# rc360detector_102415_7_15.net
KiCad netlist of a schematic drawn in EAGLE
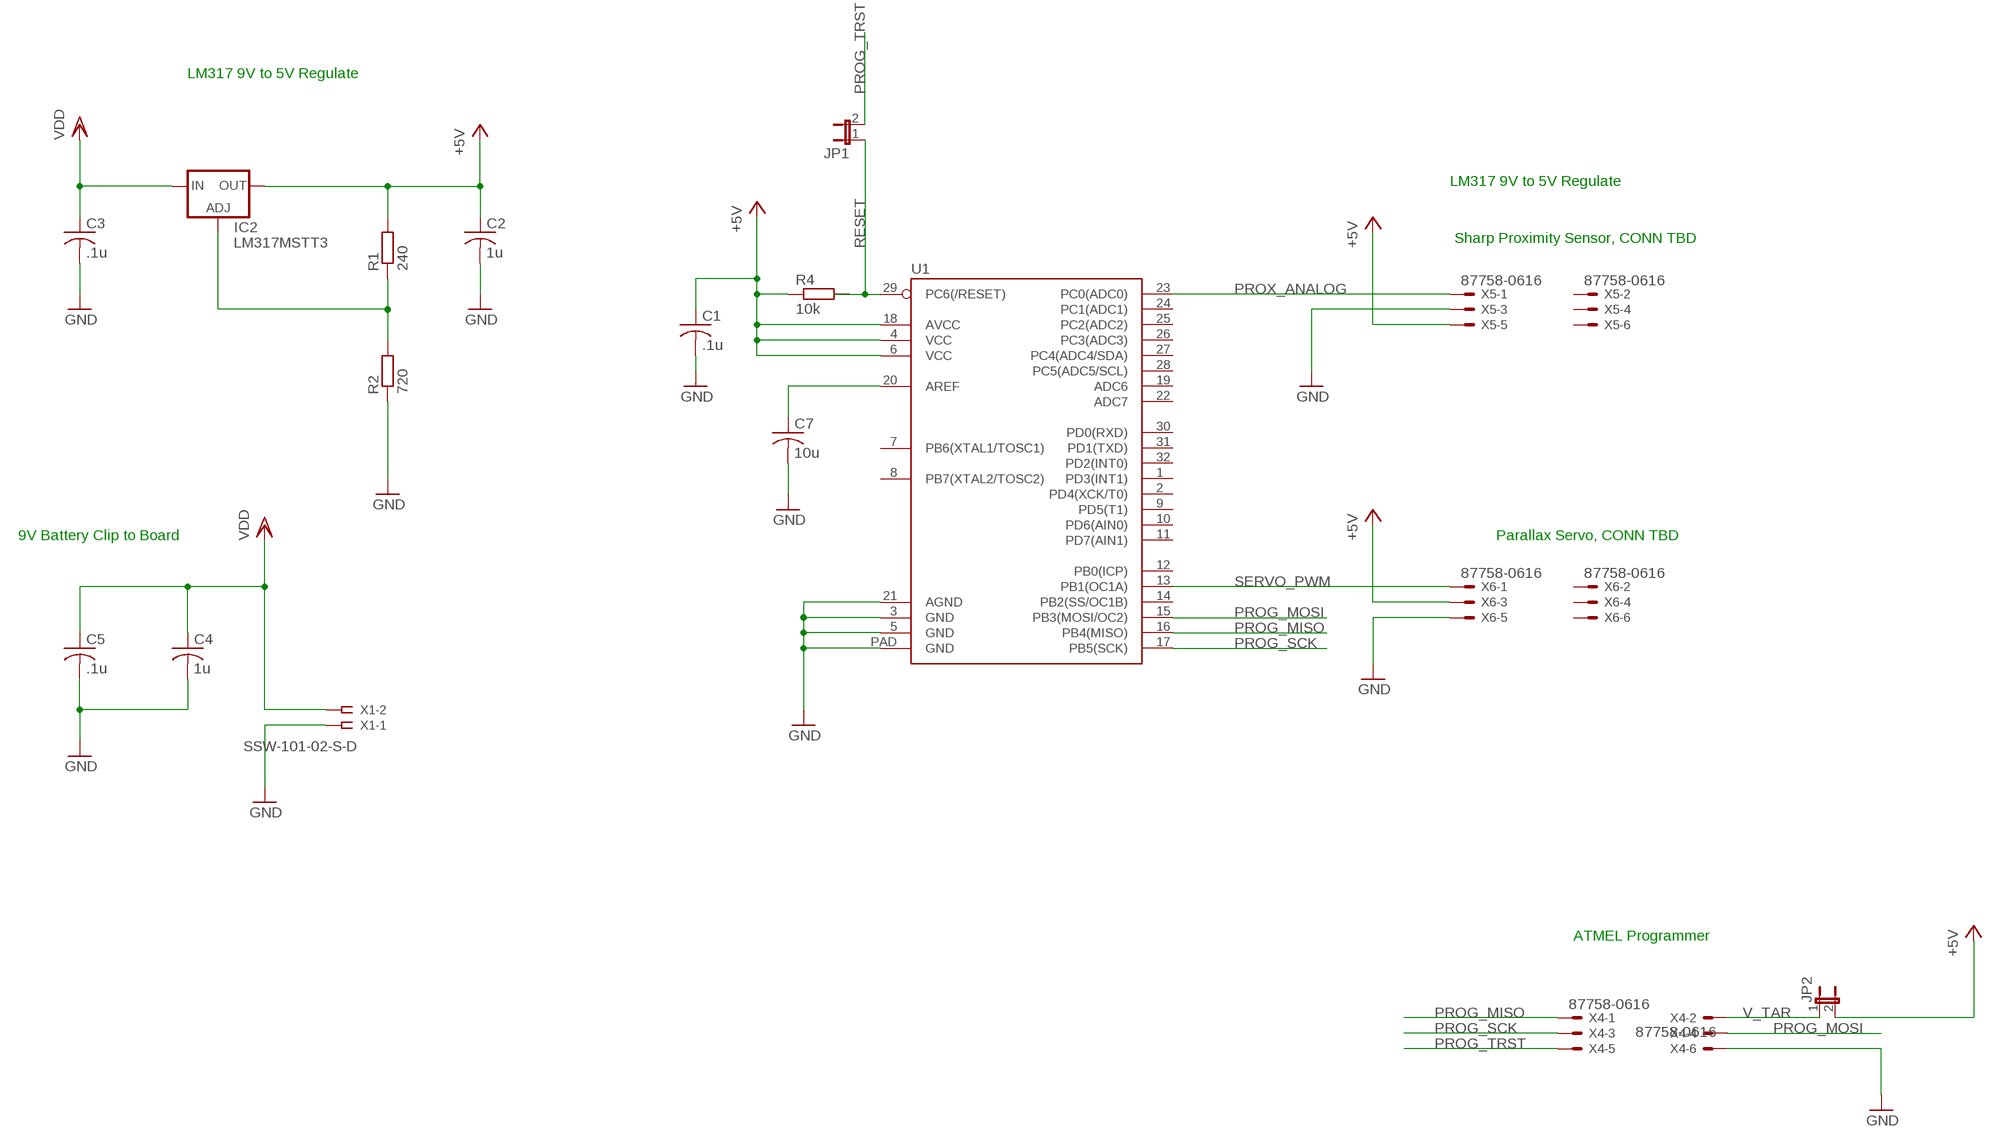
[diagram p0: schematic, sheet 1]

(export (version "E")
  (design (tool "Eeschema 10.0.6"))
  (components
    (comp (ref "C1")
      (value ".1u")
      (footprint "eagle-import:C0603")
      (libsource (lib "eagle-import") (part "C-USC0603"))
    )
    (comp (ref "C2")
      (value "1u")
      (footprint "eagle-import:C0603")
      (libsource (lib "eagle-import") (part "C-USC0603"))
    )
    (comp (ref "C3")
      (value ".1u")
      (footprint "eagle-import:C0603")
      (libsource (lib "eagle-import") (part "C-USC0603"))
    )
    (comp (ref "C4")
      (value "1u")
      (footprint "eagle-import:C0603")
      (libsource (lib "eagle-import") (part "C-USC0603"))
    )
    (comp (ref "C5")
      (value ".1u")
      (footprint "eagle-import:C0603")
      (libsource (lib "eagle-import") (part "C-USC0603"))
    )
    (comp (ref "C7")
      (value "10u")
      (footprint "eagle-import:C0603")
      (libsource (lib "eagle-import") (part "C-USC0603"))
    )
    (comp (ref "IC2")
      (value "LM317MSTT3")
      (footprint "eagle-import:SOT223")
      (libsource (lib "eagle-import") (part "LM317?MSTT3"))
    )
    (comp (ref "JP1")
      (value "JP1E")
      (footprint "eagle-import:JP1")
      (libsource (lib "eagle-import") (part "JP1E"))
    )
    (comp (ref "JP2")
      (value "JP1E")
      (footprint "eagle-import:JP1")
      (libsource (lib "eagle-import") (part "JP1E"))
    )
    (comp (ref "R1")
      (value "240")
      (footprint "eagle-import:R0603")
      (libsource (lib "eagle-import") (part "R-EU_R0603"))
    )
    (comp (ref "R2")
      (value "720")
      (footprint "eagle-import:R0603")
      (libsource (lib "eagle-import") (part "R-EU_R0603"))
    )
    (comp (ref "R4")
      (value "10k")
      (footprint "eagle-import:R0603")
      (libsource (lib "eagle-import") (part "R-EU_R0603"))
    )
    (comp (ref "U1")
      (value "ATMEGA328P_MLFMLF32")
      (footprint "eagle-import:MLF32-PAD")
      (libsource (lib "eagle-import") (part "ATMEGA328P_MLFMLF32"))
    )
    (comp (ref "X1")
      (value "SSW-101-02-S-D")
      (footprint "eagle-import:SSW-101-02-S-D")
      (libsource (lib "eagle-import") (part "SSW-101-02-S-D"))
    )
    (comp (ref "X4")
      (value "87758-0616")
      (footprint "eagle-import:87758-0616")
      (libsource (lib "eagle-import") (part "87758-0616"))
    )
    (comp (ref "X5")
      (value "87758-0616")
      (footprint "eagle-import:87758-0616")
      (libsource (lib "eagle-import") (part "87758-0616"))
    )
    (comp (ref "X6")
      (value "87758-0616")
      (footprint "eagle-import:87758-0616")
      (libsource (lib "eagle-import") (part "87758-0616"))
    )
  )
  (nets
    (net (code "1") (name "+5V") (class "Default")
      (node (ref "C1") (pin "1") (pinfunction "1_1") (pintype "passive"))
      (node (ref "C2") (pin "1") (pinfunction "1_1") (pintype "passive"))
      (node (ref "IC2") (pin "4") (pinfunction "OUT_4") (pintype "passive"))
      (node (ref "JP2") (pin "2") (pinfunction "2_2") (pintype "passive"))
      (node (ref "R1") (pin "2") (pinfunction "2_2") (pintype "passive"))
      (node (ref "R4") (pin "1") (pinfunction "1_1") (pintype "passive"))
      (node (ref "U1") (pin "18") (pinfunction "AVCC_18") (pintype "bidirectional"))
      (node (ref "U1") (pin "4") (pinfunction "VCC_4") (pintype "bidirectional"))
      (node (ref "U1") (pin "6") (pinfunction "VCC_6") (pintype "bidirectional"))
      (node (ref "X5") (pin "5") (pinfunction "S_5") (pintype "passive"))
      (node (ref "X6") (pin "3") (pinfunction "S_3") (pintype "passive"))
    )
    (net (code "2") (name "/PROG_MISO") (class "Default")
      (node (ref "U1") (pin "16") (pinfunction "PB4(MISO)_16") (pintype "bidirectional"))
      (node (ref "X4") (pin "1") (pinfunction "S_1") (pintype "passive"))
    )
    (net (code "3") (name "/PROG_MOSI") (class "Default")
      (node (ref "U1") (pin "15") (pinfunction "PB3(MOSI/OC2)_15") (pintype "bidirectional"))
      (node (ref "X4") (pin "4") (pinfunction "S_4") (pintype "passive"))
    )
    (net (code "4") (name "/PROG_SCK") (class "Default")
      (node (ref "U1") (pin "17") (pinfunction "PB5(SCK)_17") (pintype "bidirectional"))
      (node (ref "X4") (pin "3") (pinfunction "S_3") (pintype "passive"))
    )
    (net (code "5") (name "/PROG_TRST") (class "Default")
      (node (ref "JP1") (pin "2") (pinfunction "2_2") (pintype "passive"))
      (node (ref "X4") (pin "5") (pinfunction "S_5") (pintype "passive"))
    )
    (net (code "6") (name "/PROX_ANALOG") (class "Default")
      (node (ref "U1") (pin "23") (pinfunction "PC0(ADC0)_23") (pintype "bidirectional"))
      (node (ref "X5") (pin "1") (pinfunction "S_1") (pintype "passive"))
    )
    (net (code "7") (name "/RESET") (class "Default")
      (node (ref "JP1") (pin "1") (pinfunction "1_1") (pintype "passive"))
      (node (ref "R4") (pin "2") (pinfunction "2_2") (pintype "passive"))
      (node (ref "U1") (pin "29") (pinfunction "PC6(/RESET)_29") (pintype "bidirectional"))
    )
    (net (code "8") (name "/SERVO_PWM") (class "Default")
      (node (ref "U1") (pin "13") (pinfunction "PB1(OC1A)_13") (pintype "bidirectional"))
      (node (ref "X6") (pin "1") (pinfunction "S_1") (pintype "passive"))
    )
    (net (code "9") (name "/V_TAR") (class "Default")
      (node (ref "JP2") (pin "1") (pinfunction "1_1") (pintype "passive"))
      (node (ref "X4") (pin "2") (pinfunction "S_2") (pintype "passive"))
    )
    (net (code "10") (name "GND") (class "Default")
      (node (ref "C1") (pin "2") (pinfunction "2_2") (pintype "passive"))
      (node (ref "C2") (pin "2") (pinfunction "2_2") (pintype "passive"))
      (node (ref "C3") (pin "2") (pinfunction "2_2") (pintype "passive"))
      (node (ref "C4") (pin "2") (pinfunction "2_2") (pintype "passive"))
      (node (ref "C5") (pin "2") (pinfunction "2_2") (pintype "passive"))
      (node (ref "C7") (pin "2") (pinfunction "2_2") (pintype "passive"))
      (node (ref "R2") (pin "1") (pinfunction "1_1") (pintype "passive"))
      (node (ref "U1") (pin "21") (pinfunction "AGND_21") (pintype "bidirectional"))
      (node (ref "U1") (pin "3") (pinfunction "GND_3") (pintype "bidirectional"))
      (node (ref "U1") (pin "5") (pinfunction "GND_5") (pintype "bidirectional"))
      (node (ref "U1") (pin "PAD") (pinfunction "GND_PAD") (pintype "bidirectional"))
      (node (ref "X1") (pin "1") (pinfunction "1_1") (pintype "passive"))
      (node (ref "X4") (pin "6") (pinfunction "S_6") (pintype "passive"))
      (node (ref "X5") (pin "3") (pinfunction "S_3") (pintype "passive"))
      (node (ref "X6") (pin "5") (pinfunction "S_5") (pintype "passive"))
    )
    (net (code "11") (name "Net-(IC2-ADJ)") (class "Default")
      (node (ref "IC2") (pin "1") (pinfunction "ADJ_1") (pintype "input"))
      (node (ref "R1") (pin "1") (pinfunction "1_1") (pintype "passive"))
      (node (ref "R2") (pin "2") (pinfunction "2_2") (pintype "passive"))
    )
    (net (code "12") (name "Net-(U1-AREF)") (class "Default")
      (node (ref "C7") (pin "1") (pinfunction "1_1") (pintype "passive"))
      (node (ref "U1") (pin "20") (pinfunction "AREF_20") (pintype "bidirectional"))
    )
    (net (code "13") (name "VDD") (class "Default")
      (node (ref "C3") (pin "1") (pinfunction "1_1") (pintype "passive"))
      (node (ref "C4") (pin "1") (pinfunction "1_1") (pintype "passive"))
      (node (ref "C5") (pin "1") (pinfunction "1_1") (pintype "passive"))
      (node (ref "IC2") (pin "3") (pinfunction "IN_3") (pintype "input"))
      (node (ref "X1") (pin "2") (pinfunction "1_2") (pintype "passive"))
    )
    (net (code "14") (name "unconnected-(U1-ADC6-Pad19)") (class "Default")
      (node (ref "U1") (pin "19") (pinfunction "ADC6_19") (pintype "bidirectional"))
    )
    (net (code "15") (name "unconnected-(U1-ADC7-Pad22)") (class "Default")
      (node (ref "U1") (pin "22") (pinfunction "ADC7_22") (pintype "bidirectional"))
    )
    (net (code "16") (name "unconnected-(U1-PB0(ICP)-Pad12)") (class "Default")
      (node (ref "U1") (pin "12") (pinfunction "PB0(ICP)_12") (pintype "bidirectional"))
    )
    (net (code "17") (name "unconnected-(U1-PB2(SS{slash}OC1B)-Pad14)") (class "Default")
      (node (ref "U1") (pin "14") (pinfunction "PB2(SS/OC1B)_14") (pintype "bidirectional"))
    )
    (net (code "18") (name "unconnected-(U1-PB6(XTAL1{slash}TOSC1)-Pad7)") (class "Default")
      (node (ref "U1") (pin "7") (pinfunction "PB6(XTAL1/TOSC1)_7") (pintype "bidirectional"))
    )
    (net (code "19") (name "unconnected-(U1-PB7(XTAL2{slash}TOSC2)-Pad8)") (class "Default")
      (node (ref "U1") (pin "8") (pinfunction "PB7(XTAL2/TOSC2)_8") (pintype "bidirectional"))
    )
    (net (code "20") (name "unconnected-(U1-PC1(ADC1)-Pad24)") (class "Default")
      (node (ref "U1") (pin "24") (pinfunction "PC1(ADC1)_24") (pintype "bidirectional"))
    )
    (net (code "21") (name "unconnected-(U1-PC2(ADC2)-Pad25)") (class "Default")
      (node (ref "U1") (pin "25") (pinfunction "PC2(ADC2)_25") (pintype "bidirectional"))
    )
    (net (code "22") (name "unconnected-(U1-PC3(ADC3)-Pad26)") (class "Default")
      (node (ref "U1") (pin "26") (pinfunction "PC3(ADC3)_26") (pintype "bidirectional"))
    )
    (net (code "23") (name "unconnected-(U1-PC4(ADC4{slash}SDA)-Pad27)") (class "Default")
      (node (ref "U1") (pin "27") (pinfunction "PC4(ADC4/SDA)_27") (pintype "bidirectional"))
    )
    (net (code "24") (name "unconnected-(U1-PC5(ADC5{slash}SCL)-Pad28)") (class "Default")
      (node (ref "U1") (pin "28") (pinfunction "PC5(ADC5/SCL)_28") (pintype "bidirectional"))
    )
    (net (code "25") (name "unconnected-(U1-PD0(RXD)-Pad30)") (class "Default")
      (node (ref "U1") (pin "30") (pinfunction "PD0(RXD)_30") (pintype "bidirectional"))
    )
    (net (code "26") (name "unconnected-(U1-PD1(TXD)-Pad31)") (class "Default")
      (node (ref "U1") (pin "31") (pinfunction "PD1(TXD)_31") (pintype "bidirectional"))
    )
    (net (code "27") (name "unconnected-(U1-PD2(INT0)-Pad32)") (class "Default")
      (node (ref "U1") (pin "32") (pinfunction "PD2(INT0)_32") (pintype "bidirectional"))
    )
    (net (code "28") (name "unconnected-(U1-PD3(INT1)-Pad1)") (class "Default")
      (node (ref "U1") (pin "1") (pinfunction "PD3(INT1)_1") (pintype "bidirectional"))
    )
    (net (code "29") (name "unconnected-(U1-PD4(XCK{slash}T0)-Pad2)") (class "Default")
      (node (ref "U1") (pin "2") (pinfunction "PD4(XCK/T0)_2") (pintype "bidirectional"))
    )
    (net (code "30") (name "unconnected-(U1-PD5(T1)-Pad9)") (class "Default")
      (node (ref "U1") (pin "9") (pinfunction "PD5(T1)_9") (pintype "bidirectional"))
    )
    (net (code "31") (name "unconnected-(U1-PD6(AIN0)-Pad10)") (class "Default")
      (node (ref "U1") (pin "10") (pinfunction "PD6(AIN0)_10") (pintype "bidirectional"))
    )
    (net (code "32") (name "unconnected-(U1-PD7(AIN1)-Pad11)") (class "Default")
      (node (ref "U1") (pin "11") (pinfunction "PD7(AIN1)_11") (pintype "bidirectional"))
    )
    (net (code "33") (name "unconnected-(X5B-S-Pad2)") (class "Default")
      (node (ref "X5") (pin "2") (pinfunction "S_2") (pintype "passive"))
    )
    (net (code "34") (name "unconnected-(X5D-S-Pad4)") (class "Default")
      (node (ref "X5") (pin "4") (pinfunction "S_4") (pintype "passive"))
    )
    (net (code "35") (name "unconnected-(X5F-S-Pad6)") (class "Default")
      (node (ref "X5") (pin "6") (pinfunction "S_6") (pintype "passive"))
    )
    (net (code "36") (name "unconnected-(X6B-S-Pad2)") (class "Default")
      (node (ref "X6") (pin "2") (pinfunction "S_2") (pintype "passive"))
    )
    (net (code "37") (name "unconnected-(X6D-S-Pad4)") (class "Default")
      (node (ref "X6") (pin "4") (pinfunction "S_4") (pintype "passive"))
    )
    (net (code "38") (name "unconnected-(X6F-S-Pad6)") (class "Default")
      (node (ref "X6") (pin "6") (pinfunction "S_6") (pintype "passive"))
    )
  )
)
